# mcu.net
KiCad netlist of a schematic drawn in Altium Designer
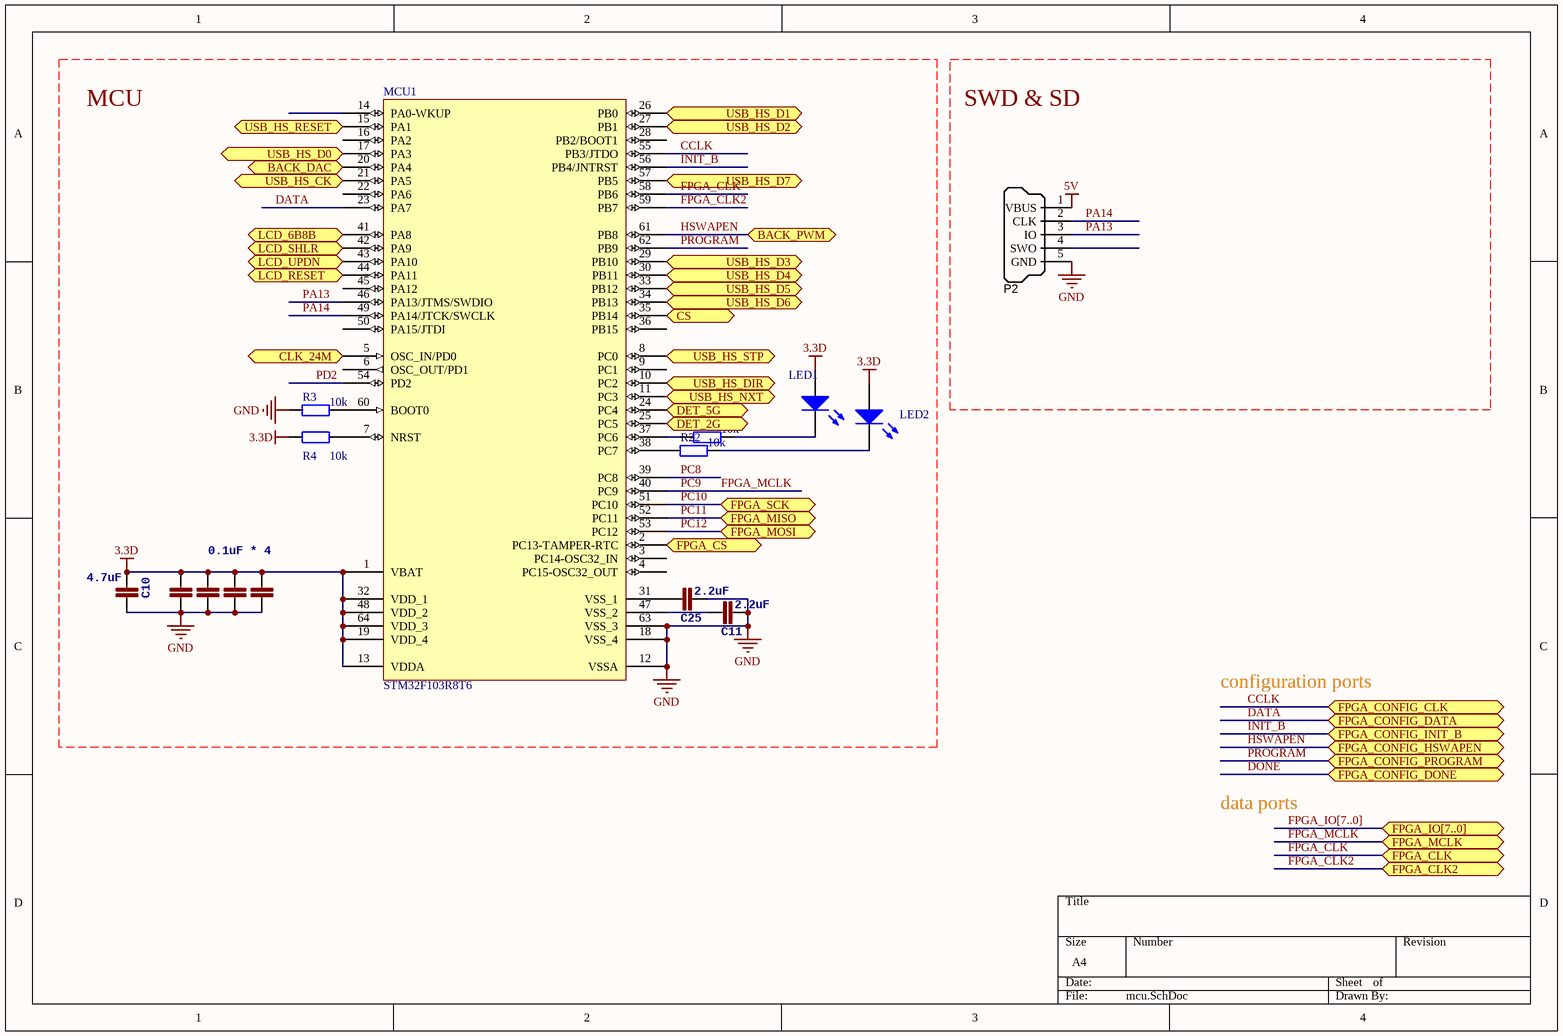
[diagram p0: mcu.SchDoc]

(export (version "E")
  (design (tool "Eeschema 10.0.6"))
  (components
    (comp (ref "C4")
      (value "0.1uF * 4")
      (footprint "0402")
      (description "<b>Capacitor</b>\nStandard 0603 ceramic capacitor, and 0.1\" leaded capacitor.")
      (fields (field (name "PARTNO") "CC0402ZRY5V7BB104"))
      (libsource (lib "*") (part "CAP0402-CAP"))
    )
    (comp (ref "C5")
      (value "1n")
      (footprint "0402")
      (description "<b>Capacitor</b>\nStandard 0603 ceramic capacitor, and 0.1\" leaded capacitor.")
      (fields (field (name "PARTNO") "CC0402ZRY5V7BB104"))
      (libsource (lib "pixhawk2") (part "CAP0402-CAP"))
    )
    (comp (ref "C6")
      (value "1n")
      (footprint "0402")
      (description "<b>Capacitor</b>\nStandard 0603 ceramic capacitor, and 0.1\" leaded capacitor.")
      (fields (field (name "PARTNO") "CC0402ZRY5V7BB104"))
      (libsource (lib "pixhawk2") (part "CAP0402-CAP"))
    )
    (comp (ref "C7")
      (value "1n")
      (footprint "0402")
      (description "<b>Capacitor</b>\nStandard 0603 ceramic capacitor, and 0.1\" leaded capacitor.")
      (fields (field (name "PARTNO") "CC0402ZRY5V7BB104"))
      (libsource (lib "pixhawk2") (part "CAP0402-CAP"))
    )
    (comp (ref "C10")
      (value "4.7uF")
      (footprint "0603")
      (description "<b>Capacitor</b>\nStandard 0603 ceramic capacitor, and 0.1\" leaded capacitor.")
      (fields (field (name "PARTNO") "CC0402ZRY5V7BB104"))
      (libsource (lib "pixhawk2") (part "CAP0402-CAP"))
    )
    (comp (ref "C11")
      (value "2.2uF")
      (footprint "0603")
      (description "<b>Capacitor</b>\nStandard 0603 ceramic capacitor, and 0.1\" leaded capacitor.")
      (fields (field (name "PARTNO") "CC0402ZRY5V7BB104"))
      (libsource (lib "") (part "CAP0402-CAP_1"))
    )
    (comp (ref "C25")
      (value "2.2uF")
      (footprint "0603")
      (description "<b>Capacitor</b>\nStandard 0603 ceramic capacitor, and 0.1\" leaded capacitor.")
      (fields (field (name "PARTNO") "CC0402ZRY5V7BB104"))
      (libsource (lib "") (part "CAP0402-CAP_1"))
    )
    (comp (ref "LED1")
      (value "LED0")
      (footprint "0603")
      (description "Typical INFRARED GaAs LED")
      (fields (field (name "PUBLISHER") "Altium Limited"))
      (libsource (lib "Miscellaneous Devices") (part "LED0"))
    )
    (comp (ref "LED2")
      (value "LED0")
      (footprint "0603")
      (description "Typical INFRARED GaAs LED")
      (fields (field (name "PUBLISHER") "Altium Limited"))
      (libsource (lib "Miscellaneous Devices") (part "LED0"))
    )
    (comp (ref "MCU1")
      (value "STM32F103R8T6")
      (footprint "LQFP64_N")
      (description "STM32 ARM-based 32-bit MCU with 64 Kbytes Flash, 64-pin LQFP, Industrial Temperature")
      (fields (field (name "PUBLISHER") "*"))
      (libsource (lib "ST Microcontroller 32-Bit STM32 SCH") (part "STM32F103R8T6"))
    )
    (comp (ref "P2")
      (value "SWD_MicroUSB")
      (footprint "MICRO-YZX")
      (description "Connector SMD USB Micro Type B middle mount")
      (libsource (lib "sch") (part "SWD_MicroUSB"))
    )
    (comp (ref "R3")
      (value "10k")
      (footprint "0402")
      (description "Resistor")
      (fields (field (name "PUBLISHER") "Altium Limited"))
      (libsource (lib "") (part "Res2_1"))
    )
    (comp (ref "R4")
      (value "10k")
      (footprint "0402")
      (description "Resistor")
      (fields (field (name "PUBLISHER") "Altium Limited"))
      (libsource (lib "Miscellaneous Devices") (part "Res2"))
    )
    (comp (ref "R21")
      (value "10k")
      (footprint "0402")
      (description "Resistor")
      (fields (field (name "PUBLISHER") "Altium Limited"))
      (libsource (lib "") (part "Res2_1"))
    )
    (comp (ref "R22")
      (value "10k")
      (footprint "0402")
      (description "Resistor")
      (fields (field (name "PUBLISHER") "Altium Limited"))
      (libsource (lib "") (part "Res2_1"))
    )
  )
  (nets
    (net (code "9") (name "/BACK_DAC") (class "Default")
      (node (ref "MCU1") (pin "20") (pinfunction "PA4_20") (pintype "bidirectional"))
    )
    (net (code "10") (name "/CCLK") (class "Default")
      (node (ref "MCU1") (pin "55") (pinfunction "PB3/JTDO_55") (pintype "bidirectional"))
    )
    (net (code "11") (name "/CLK_24M") (class "Default")
      (node (ref "MCU1") (pin "5") (pinfunction "OSC_IN/PD0_5") (pintype "input"))
    )
    (net (code "12") (name "/CS") (class "Default")
      (node (ref "MCU1") (pin "35") (pinfunction "PB14_35") (pintype "bidirectional"))
    )
    (net (code "13") (name "/DATA") (class "Default")
      (node (ref "MCU1") (pin "23") (pinfunction "PA7_23") (pintype "bidirectional"))
    )
    (net (code "14") (name "/DET_2G") (class "Default")
      (node (ref "MCU1") (pin "25") (pinfunction "PC5_25") (pintype "bidirectional"))
    )
    (net (code "15") (name "/DET_5G") (class "Default")
      (node (ref "MCU1") (pin "24") (pinfunction "PC4_24") (pintype "bidirectional"))
    )
    (net (code "17") (name "/FPGA_CLK") (class "Default")
      (node (ref "MCU1") (pin "58") (pinfunction "PB6_58") (pintype "bidirectional"))
    )
    (net (code "18") (name "/FPGA_CLK2") (class "Default")
      (node (ref "MCU1") (pin "59") (pinfunction "PB7_59") (pintype "bidirectional"))
    )
    (net (code "19") (name "/FPGA_CS") (class "Default")
      (node (ref "MCU1") (pin "2") (pinfunction "PC13-TAMPER-RTC_2") (pintype "bidirectional"))
    )
    (net (code "21") (name "/FPGA_MCLK") (class "Default")
      (node (ref "MCU1") (pin "40") (pinfunction "PC9_40") (pintype "bidirectional"))
    )
    (net (code "22") (name "/HSWAPEN") (class "Default")
      (node (ref "MCU1") (pin "61") (pinfunction "PB8_61") (pintype "bidirectional"))
    )
    (net (code "23") (name "/INIT_B") (class "Default")
      (node (ref "MCU1") (pin "56") (pinfunction "PB4/JNTRST_56") (pintype "bidirectional"))
    )
    (net (code "24") (name "/LCD_6B8B") (class "Default")
      (node (ref "MCU1") (pin "41") (pinfunction "PA8_41") (pintype "bidirectional"))
    )
    (net (code "25") (name "/LCD_RESET") (class "Default")
      (node (ref "MCU1") (pin "44") (pinfunction "PA11_44") (pintype "bidirectional"))
    )
    (net (code "26") (name "/LCD_SHLR") (class "Default")
      (node (ref "MCU1") (pin "42") (pinfunction "PA9_42") (pintype "bidirectional"))
    )
    (net (code "27") (name "/LCD_UPDN") (class "Default")
      (node (ref "MCU1") (pin "43") (pinfunction "PA10_43") (pintype "bidirectional"))
    )
    (net (code "28") (name "/PA13") (class "Default")
      (node (ref "MCU1") (pin "46") (pinfunction "PA13/JTMS/SWDIO_46") (pintype "bidirectional"))
      (node (ref "P2") (pin "3") (pinfunction "IO_3") (pintype "passive"))
    )
    (net (code "29") (name "/PA14") (class "Default")
      (node (ref "MCU1") (pin "49") (pinfunction "PA14/JTCK/SWCLK_49") (pintype "bidirectional"))
      (node (ref "P2") (pin "2") (pinfunction "CLK_2") (pintype "passive"))
    )
    (net (code "30") (name "/PC8") (class "Default")
      (node (ref "MCU1") (pin "39") (pinfunction "PC8_39") (pintype "bidirectional"))
    )
    (net (code "31") (name "/PC10") (class "Default")
      (node (ref "MCU1") (pin "51") (pinfunction "PC10_51") (pintype "bidirectional"))
    )
    (net (code "32") (name "/PC11") (class "Default")
      (node (ref "MCU1") (pin "52") (pinfunction "PC11_52") (pintype "bidirectional"))
    )
    (net (code "33") (name "/PC12") (class "Default")
      (node (ref "MCU1") (pin "53") (pinfunction "PC12_53") (pintype "bidirectional"))
    )
    (net (code "34") (name "/PD2") (class "Default")
      (node (ref "MCU1") (pin "54") (pinfunction "PD2_54") (pintype "bidirectional"))
    )
    (net (code "35") (name "/PROGRAM") (class "Default")
      (node (ref "MCU1") (pin "62") (pinfunction "PB9_62") (pintype "bidirectional"))
    )
    (net (code "36") (name "/USB_HS_CK") (class "Default")
      (node (ref "MCU1") (pin "21") (pinfunction "PA5_21") (pintype "bidirectional"))
    )
    (net (code "37") (name "/USB_HS_D0") (class "Default")
      (node (ref "MCU1") (pin "17") (pinfunction "PA3_17") (pintype "bidirectional"))
    )
    (net (code "38") (name "/USB_HS_D1") (class "Default")
      (node (ref "MCU1") (pin "26") (pinfunction "PB0_26") (pintype "bidirectional"))
    )
    (net (code "39") (name "/USB_HS_D2") (class "Default")
      (node (ref "MCU1") (pin "27") (pinfunction "PB1_27") (pintype "bidirectional"))
    )
    (net (code "40") (name "/USB_HS_D3") (class "Default")
      (node (ref "MCU1") (pin "29") (pinfunction "PB10_29") (pintype "bidirectional"))
    )
    (net (code "41") (name "/USB_HS_D4") (class "Default")
      (node (ref "MCU1") (pin "30") (pinfunction "PB11_30") (pintype "bidirectional"))
    )
    (net (code "42") (name "/USB_HS_D5") (class "Default")
      (node (ref "MCU1") (pin "33") (pinfunction "PB12_33") (pintype "bidirectional"))
    )
    (net (code "43") (name "/USB_HS_D6") (class "Default")
      (node (ref "MCU1") (pin "34") (pinfunction "PB13_34") (pintype "bidirectional"))
    )
    (net (code "44") (name "/USB_HS_D7") (class "Default")
      (node (ref "MCU1") (pin "57") (pinfunction "PB5_57") (pintype "bidirectional"))
    )
    (net (code "45") (name "/USB_HS_DIR") (class "Default")
      (node (ref "MCU1") (pin "10") (pinfunction "PC2_10") (pintype "bidirectional"))
    )
    (net (code "46") (name "/USB_HS_NXT") (class "Default")
      (node (ref "MCU1") (pin "11") (pinfunction "PC3_11") (pintype "bidirectional"))
    )
    (net (code "47") (name "/USB_HS_RESET") (class "Default")
      (node (ref "MCU1") (pin "15") (pinfunction "PA1_15") (pintype "bidirectional"))
    )
    (net (code "48") (name "/USB_HS_STP") (class "Default")
      (node (ref "MCU1") (pin "8") (pinfunction "PC0_8") (pintype "bidirectional"))
    )
    (net (code "49") (name "3.3D") (class "Default")
      (node (ref "C10") (pin "2") (pinfunction "2_2") (pintype "passive"))
      (node (ref "C4") (pin "2") (pinfunction "2_2") (pintype "passive"))
      (node (ref "C5") (pin "2") (pinfunction "2_2") (pintype "passive"))
      (node (ref "C6") (pin "2") (pinfunction "2_2") (pintype "passive"))
      (node (ref "C7") (pin "2") (pinfunction "2_2") (pintype "passive"))
      (node (ref "LED1") (pin "1") (pinfunction "A_1") (pintype "passive"))
      (node (ref "LED2") (pin "1") (pinfunction "A_1") (pintype "passive"))
      (node (ref "MCU1") (pin "1") (pinfunction "VBAT_1") (pintype "power_in"))
      (node (ref "MCU1") (pin "13") (pinfunction "VDDA_13") (pintype "power_in"))
      (node (ref "MCU1") (pin "19") (pinfunction "VDD_4_19") (pintype "power_in"))
      (node (ref "MCU1") (pin "32") (pinfunction "VDD_1_32") (pintype "power_in"))
      (node (ref "MCU1") (pin "48") (pinfunction "VDD_2_48") (pintype "power_in"))
      (node (ref "MCU1") (pin "64") (pinfunction "VDD_3_64") (pintype "power_in"))
      (node (ref "R4") (pin "2") (pinfunction "2_2") (pintype "passive"))
    )
    (net (code "50") (name "5V") (class "Default")
      (node (ref "P2") (pin "1") (pinfunction "VBUS_1") (pintype "passive"))
    )
    (net (code "51") (name "GND") (class "Default")
      (node (ref "C10") (pin "1") (pinfunction "1_1") (pintype "passive"))
      (node (ref "C11") (pin "2") (pinfunction "2_2") (pintype "passive"))
      (node (ref "C25") (pin "2") (pinfunction "2_2") (pintype "passive"))
      (node (ref "C4") (pin "1") (pinfunction "1_1") (pintype "passive"))
      (node (ref "C5") (pin "1") (pinfunction "1_1") (pintype "passive"))
      (node (ref "C6") (pin "1") (pinfunction "1_1") (pintype "passive"))
      (node (ref "C7") (pin "1") (pinfunction "1_1") (pintype "passive"))
      (node (ref "MCU1") (pin "12") (pinfunction "VSSA_12") (pintype "power_in"))
      (node (ref "MCU1") (pin "18") (pinfunction "VSS_4_18") (pintype "power_in"))
      (node (ref "MCU1") (pin "63") (pinfunction "VSS_3_63") (pintype "power_in"))
      (node (ref "P2") (pin "5") (pinfunction "GND_5") (pintype "passive"))
      (node (ref "R3") (pin "1") (pinfunction "1_1") (pintype "passive"))
    )
    (net (code "52") (name "Net-(LED1-K)") (class "Default")
      (node (ref "LED1") (pin "2") (pinfunction "K_2") (pintype "passive"))
      (node (ref "R21") (pin "2") (pinfunction "2_2") (pintype "passive"))
    )
    (net (code "53") (name "Net-(LED2-K)") (class "Default")
      (node (ref "LED2") (pin "2") (pinfunction "K_2") (pintype "passive"))
      (node (ref "R22") (pin "2") (pinfunction "2_2") (pintype "passive"))
    )
    (net (code "54") (name "Net-(MCU1-BOOT0)") (class "Default")
      (node (ref "MCU1") (pin "60") (pinfunction "BOOT0_60") (pintype "input"))
      (node (ref "R3") (pin "2") (pinfunction "2_2") (pintype "passive"))
    )
    (net (code "55") (name "Net-(MCU1-NRST)") (class "Default")
      (node (ref "MCU1") (pin "7") (pinfunction "NRST_7") (pintype "bidirectional"))
      (node (ref "R4") (pin "1") (pinfunction "1_1") (pintype "passive"))
    )
    (net (code "56") (name "Net-(MCU1-PC6)") (class "Default")
      (node (ref "MCU1") (pin "37") (pinfunction "PC6_37") (pintype "bidirectional"))
      (node (ref "R21") (pin "1") (pinfunction "1_1") (pintype "passive"))
    )
    (net (code "57") (name "Net-(MCU1-PC7)") (class "Default")
      (node (ref "MCU1") (pin "38") (pinfunction "PC7_38") (pintype "bidirectional"))
      (node (ref "R22") (pin "1") (pinfunction "1_1") (pintype "passive"))
    )
    (net (code "58") (name "Net-(MCU1-VSS_1)") (class "Default")
      (node (ref "C25") (pin "1") (pinfunction "1_1") (pintype "passive"))
      (node (ref "MCU1") (pin "31") (pinfunction "VSS_1_31") (pintype "power_in"))
    )
    (net (code "59") (name "Net-(MCU1-VSS_2)") (class "Default")
      (node (ref "C11") (pin "1") (pinfunction "1_1") (pintype "passive"))
      (node (ref "MCU1") (pin "47") (pinfunction "VSS_2_47") (pintype "power_in"))
    )
    (net (code "60") (name "unconnected-(MCU1-OSC_OUT{slash}PD1-Pad6)") (class "Default")
      (node (ref "MCU1") (pin "6") (pinfunction "OSC_OUT/PD1_6") (pintype "output"))
    )
    (net (code "61") (name "unconnected-(MCU1-PA0-WKUP-Pad14)") (class "Default")
      (node (ref "MCU1") (pin "14") (pinfunction "PA0-WKUP_14") (pintype "bidirectional"))
    )
    (net (code "62") (name "unconnected-(MCU1-PA2-Pad16)") (class "Default")
      (node (ref "MCU1") (pin "16") (pinfunction "PA2_16") (pintype "bidirectional"))
    )
    (net (code "63") (name "unconnected-(MCU1-PA6-Pad22)") (class "Default")
      (node (ref "MCU1") (pin "22") (pinfunction "PA6_22") (pintype "bidirectional"))
    )
    (net (code "64") (name "unconnected-(MCU1-PA12-Pad45)") (class "Default")
      (node (ref "MCU1") (pin "45") (pinfunction "PA12_45") (pintype "bidirectional"))
    )
    (net (code "65") (name "unconnected-(MCU1-PA15{slash}JTDI-Pad50)") (class "Default")
      (node (ref "MCU1") (pin "50") (pinfunction "PA15/JTDI_50") (pintype "bidirectional"))
    )
    (net (code "66") (name "unconnected-(MCU1-PB2{slash}BOOT1-Pad28)") (class "Default")
      (node (ref "MCU1") (pin "28") (pinfunction "PB2/BOOT1_28") (pintype "bidirectional"))
    )
    (net (code "67") (name "unconnected-(MCU1-PB15-Pad36)") (class "Default")
      (node (ref "MCU1") (pin "36") (pinfunction "PB15_36") (pintype "bidirectional"))
    )
    (net (code "68") (name "unconnected-(MCU1-PC1-Pad9)") (class "Default")
      (node (ref "MCU1") (pin "9") (pinfunction "PC1_9") (pintype "bidirectional"))
    )
    (net (code "69") (name "unconnected-(MCU1-PC14-OSC32_IN-Pad3)") (class "Default")
      (node (ref "MCU1") (pin "3") (pinfunction "PC14-OSC32_IN_3") (pintype "bidirectional"))
    )
    (net (code "70") (name "unconnected-(MCU1-PC15-OSC32_OUT-Pad4)") (class "Default")
      (node (ref "MCU1") (pin "4") (pinfunction "PC15-OSC32_OUT_4") (pintype "bidirectional"))
    )
    (net (code "71") (name "unconnected-(P2-SWO-Pad4)") (class "Default")
      (node (ref "P2") (pin "4") (pinfunction "SWO_4") (pintype "passive"))
    )
  )
)
